# DEGREE_V3.net
KiCad netlist of a schematic drawn in EAGLE
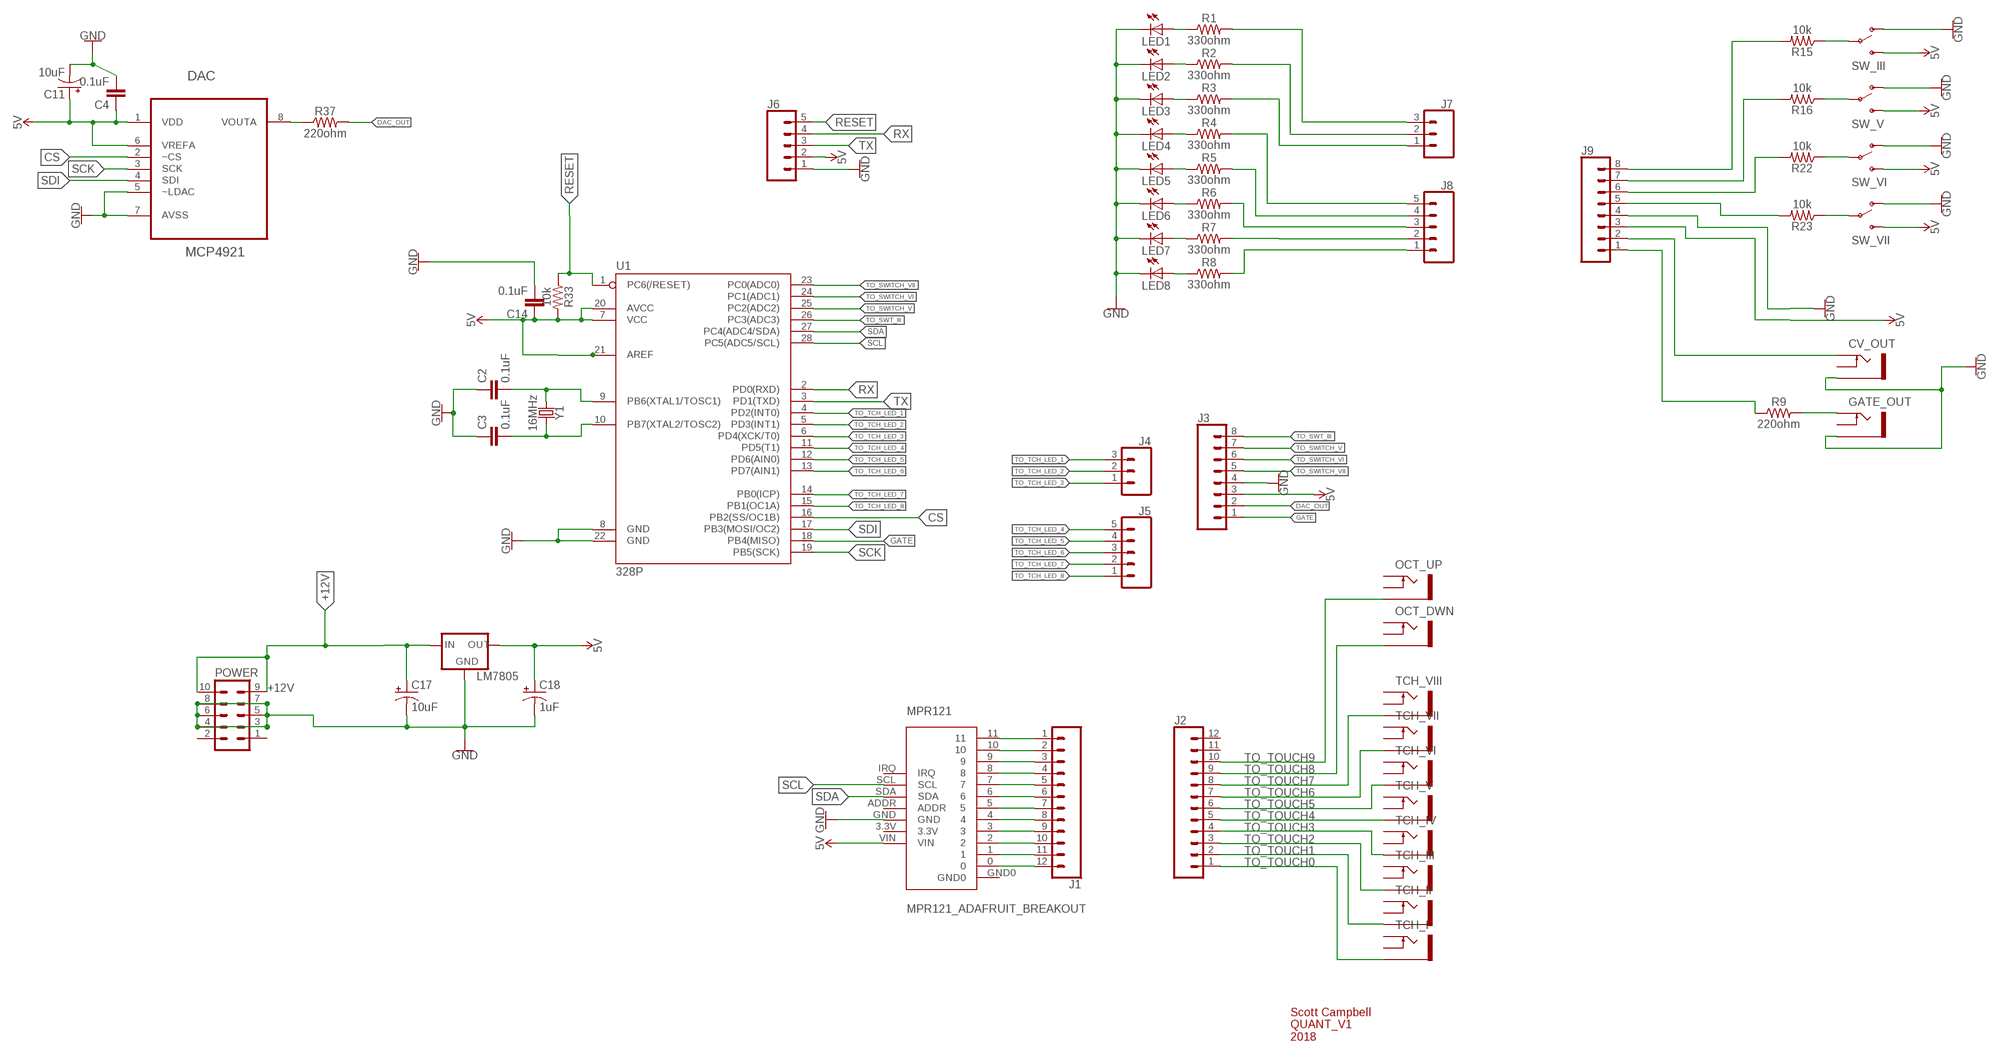
[diagram p0: schematic, sheet 1]

(export (version "E")
  (design (tool "Eeschema 10.0.6"))
  (components
    (comp (ref "C2")
      (value "0.1uF")
      (footprint "eagle-import:CAP-PTH-SMALL-KIT")
      (libsource (lib "eagle-import") (part "0.1UF-KIT-EZ-50V-20%"))
    )
    (comp (ref "C3")
      (value "0.1uF")
      (footprint "eagle-import:CAP-PTH-SMALL-KIT")
      (libsource (lib "eagle-import") (part "0.1UF-KIT-EZ-50V-20%"))
    )
    (comp (ref "C4")
      (value "0.1uF")
      (footprint "eagle-import:CAP-PTH-SMALL-KIT")
      (libsource (lib "eagle-import") (part "0.1UF-KIT-EZ-50V-20%"))
    )
    (comp (ref "C11")
      (value "10uF")
      (footprint "eagle-import:CPOL-RADIAL-2.5MM-5MM")
      (libsource (lib "eagle-import") (part "10UF-POLAR-RADIAL-2.5MM-25V-20%"))
    )
    (comp (ref "C14")
      (value "0.1uF")
      (footprint "eagle-import:CAP-PTH-SMALL-KIT")
      (libsource (lib "eagle-import") (part "0.1UF-KIT-EZ-50V-20%"))
    )
    (comp (ref "C17")
      (value "10uF")
      (footprint "eagle-import:CPOL-RADIAL-2.5MM-5MM")
      (libsource (lib "eagle-import") (part "10UF-POLAR-RADIAL-2.5MM-25V-20%"))
    )
    (comp (ref "C18")
      (value "1uF")
      (footprint "eagle-import:CPOL-RADIAL-2.5MM-5MM")
      (libsource (lib "eagle-import") (part "10UF-POLAR-RADIAL-2.5MM-25V-20%"))
    )
    (comp (ref "CV_OUT")
      (value "CV_OUT")
      (footprint "eagle-import:WQP-PJ301M-12_JACK")
      (libsource (lib "eagle-import") (part "THONKICONNNEW"))
    )
    (comp (ref "DAC")
      (value "MCP4921")
      (footprint "eagle-import:DIP08")
      (libsource (lib "eagle-import") (part "MCP4921"))
    )
    (comp (ref "GATE_OUT")
      (value "GATE_OUT")
      (footprint "eagle-import:WQP-PJ301M-12_JACK")
      (libsource (lib "eagle-import") (part "THONKICONNNEW"))
    )
    (comp (ref "J1")
      (value "CONN_12")
      (footprint "eagle-import:1X12")
      (libsource (lib "eagle-import") (part "CONN_12"))
    )
    (comp (ref "J2")
      (value "CONN_12")
      (footprint "eagle-import:1X12")
      (libsource (lib "eagle-import") (part "CONN_12"))
    )
    (comp (ref "J3")
      (value "CONN_08\"")
      (footprint "eagle-import:1X08")
      (libsource (lib "eagle-import") (part "CONN_08{dblquote}"))
    )
    (comp (ref "J4")
      (value "CONN_03")
      (footprint "eagle-import:1X03")
      (libsource (lib "eagle-import") (part "CONN_03"))
    )
    (comp (ref "J5")
      (value "CONN_05")
      (footprint "eagle-import:1X05")
      (libsource (lib "eagle-import") (part "CONN_05"))
    )
    (comp (ref "J6")
      (value "CONN_05")
      (footprint "eagle-import:1X05")
      (libsource (lib "eagle-import") (part "CONN_05"))
    )
    (comp (ref "J7")
      (value "CONN_03")
      (footprint "eagle-import:1X03")
      (libsource (lib "eagle-import") (part "CONN_03"))
    )
    (comp (ref "J8")
      (value "CONN_05")
      (footprint "eagle-import:1X05")
      (libsource (lib "eagle-import") (part "CONN_05"))
    )
    (comp (ref "J9")
      (value "CONN_08\"")
      (footprint "eagle-import:1X08")
      (libsource (lib "eagle-import") (part "CONN_08{dblquote}"))
    )
    (comp (ref "LED1")
      (value "LED3MM")
      (footprint "eagle-import:LED3MM")
      (libsource (lib "eagle-import") (part "LED3MM"))
    )
    (comp (ref "LED2")
      (value "LED3MM")
      (footprint "eagle-import:LED3MM")
      (libsource (lib "eagle-import") (part "LED3MM"))
    )
    (comp (ref "LED3")
      (value "LED3MM")
      (footprint "eagle-import:LED3MM")
      (libsource (lib "eagle-import") (part "LED3MM"))
    )
    (comp (ref "LED4")
      (value "LED3MM")
      (footprint "eagle-import:LED3MM")
      (libsource (lib "eagle-import") (part "LED3MM"))
    )
    (comp (ref "LED5")
      (value "LED3MM")
      (footprint "eagle-import:LED3MM")
      (libsource (lib "eagle-import") (part "LED3MM"))
    )
    (comp (ref "LED6")
      (value "LED3MM")
      (footprint "eagle-import:LED3MM")
      (libsource (lib "eagle-import") (part "LED3MM"))
    )
    (comp (ref "LED7")
      (value "LED3MM")
      (footprint "eagle-import:LED3MM")
      (libsource (lib "eagle-import") (part "LED3MM"))
    )
    (comp (ref "LED8")
      (value "LED3MM")
      (footprint "eagle-import:LED3MM")
      (libsource (lib "eagle-import") (part "LED3MM"))
    )
    (comp (ref "LM7805")
      (value "V_REG_78XXTO-92_UNTESTED")
      (footprint "eagle-import:TO-92")
      (libsource (lib "eagle-import") (part "V_REG_78XXTO-92_UNTESTED"))
    )
    (comp (ref "MPR121")
      (value "MPR121_ADAFRUIT_BREAKOUT")
      (footprint "eagle-import:MPR121_ADAFRUIT_BREAKOUT")
      (libsource (lib "eagle-import") (part "MPR121_ADAFRUIT_BREAKOUT"))
    )
    (comp (ref "OCT_DWN")
      (value "THONKICONN-ESSY")
      (footprint "eagle-import:THONKICONN-ESSY")
      (libsource (lib "eagle-import") (part "THONKICONN-ESSY"))
    )
    (comp (ref "OCT_UP")
      (value "THONKICONN-ESSY")
      (footprint "eagle-import:THONKICONN-ESSY")
      (libsource (lib "eagle-import") (part "THONKICONN-ESSY"))
    )
    (comp (ref "POWER")
      (value "EURO_POWER_HEADERREGULAR")
      (footprint "eagle-import:EURO_POWER_HEADER")
      (libsource (lib "eagle-import") (part "EURO_POWER_HEADERREGULAR"))
    )
    (comp (ref "R1")
      (value "330ohm")
      (footprint "eagle-import:AXIAL-0.3")
      (libsource (lib "eagle-import") (part "1KOHM-HORIZ-1/4W-5%"))
    )
    (comp (ref "R2")
      (value "330ohm")
      (footprint "eagle-import:AXIAL-0.3")
      (libsource (lib "eagle-import") (part "1KOHM-HORIZ-1/4W-5%"))
    )
    (comp (ref "R3")
      (value "330ohm")
      (footprint "eagle-import:AXIAL-0.3")
      (libsource (lib "eagle-import") (part "1KOHM-HORIZ-1/4W-5%"))
    )
    (comp (ref "R4")
      (value "330ohm")
      (footprint "eagle-import:AXIAL-0.3")
      (libsource (lib "eagle-import") (part "1KOHM-HORIZ-1/4W-5%"))
    )
    (comp (ref "R5")
      (value "330ohm")
      (footprint "eagle-import:AXIAL-0.3")
      (libsource (lib "eagle-import") (part "1KOHM-HORIZ-1/4W-5%"))
    )
    (comp (ref "R6")
      (value "330ohm")
      (footprint "eagle-import:AXIAL-0.3")
      (libsource (lib "eagle-import") (part "1KOHM-HORIZ-1/4W-5%"))
    )
    (comp (ref "R7")
      (value "330ohm")
      (footprint "eagle-import:AXIAL-0.3")
      (libsource (lib "eagle-import") (part "1KOHM-HORIZ-1/4W-5%"))
    )
    (comp (ref "R8")
      (value "330ohm")
      (footprint "eagle-import:AXIAL-0.3")
      (libsource (lib "eagle-import") (part "1KOHM-HORIZ-1/4W-5%"))
    )
    (comp (ref "R9")
      (value "220ohm")
      (footprint "eagle-import:HORIZONTAL_RESISTOR")
      (libsource (lib "eagle-import") (part "RESISTOR_HORZ"))
    )
    (comp (ref "R15")
      (value "10k")
      (footprint "eagle-import:HORIZONTAL_RESISTOR")
      (libsource (lib "eagle-import") (part "RESISTOR_HORZ"))
    )
    (comp (ref "R16")
      (value "10k")
      (footprint "eagle-import:HORIZONTAL_RESISTOR")
      (libsource (lib "eagle-import") (part "RESISTOR_HORZ"))
    )
    (comp (ref "R22")
      (value "10k")
      (footprint "eagle-import:HORIZONTAL_RESISTOR")
      (libsource (lib "eagle-import") (part "RESISTOR_HORZ"))
    )
    (comp (ref "R23")
      (value "10k")
      (footprint "eagle-import:HORIZONTAL_RESISTOR")
      (libsource (lib "eagle-import") (part "RESISTOR_HORZ"))
    )
    (comp (ref "R33")
      (value "10k")
      (footprint "eagle-import:HORIZONTAL_RESISTOR")
      (libsource (lib "eagle-import") (part "RESISTOR_HORZ"))
    )
    (comp (ref "R37")
      (value "220ohm")
      (footprint "eagle-import:VERTICAL_RESISTOR")
      (libsource (lib "eagle-import") (part "RESISTOR_VERT"))
    )
    (comp (ref "SW_III")
      (value "SUBMINI_SPDT")
      (footprint "eagle-import:SUBMINI_TOGGLE")
      (libsource (lib "eagle-import") (part "SUBMINI_SPDT"))
    )
    (comp (ref "SW_V")
      (value "SUBMINI_SPDT")
      (footprint "eagle-import:SUBMINI_TOGGLE")
      (libsource (lib "eagle-import") (part "SUBMINI_SPDT"))
    )
    (comp (ref "SW_VI")
      (value "SUBMINI_SPDT")
      (footprint "eagle-import:SUBMINI_TOGGLE")
      (libsource (lib "eagle-import") (part "SUBMINI_SPDT"))
    )
    (comp (ref "SW_VII")
      (value "SUBMINI_SPDT")
      (footprint "eagle-import:SUBMINI_TOGGLE")
      (libsource (lib "eagle-import") (part "SUBMINI_SPDT"))
    )
    (comp (ref "TCH_I")
      (value "THONKICONN-ESSY")
      (footprint "eagle-import:THONKICONN-ESSY")
      (libsource (lib "eagle-import") (part "THONKICONN-ESSY"))
    )
    (comp (ref "TCH_II")
      (value "THONKICONN-ESSY")
      (footprint "eagle-import:THONKICONN-ESSY")
      (libsource (lib "eagle-import") (part "THONKICONN-ESSY"))
    )
    (comp (ref "TCH_III")
      (value "THONKICONN-ESSY")
      (footprint "eagle-import:THONKICONN-ESSY")
      (libsource (lib "eagle-import") (part "THONKICONN-ESSY"))
    )
    (comp (ref "TCH_IV")
      (value "THONKICONN-ESSY")
      (footprint "eagle-import:THONKICONN-ESSY")
      (libsource (lib "eagle-import") (part "THONKICONN-ESSY"))
    )
    (comp (ref "TCH_V")
      (value "THONKICONN-ESSY")
      (footprint "eagle-import:THONKICONN-ESSY")
      (libsource (lib "eagle-import") (part "THONKICONN-ESSY"))
    )
    (comp (ref "TCH_VI")
      (value "THONKICONN-ESSY")
      (footprint "eagle-import:THONKICONN-ESSY")
      (libsource (lib "eagle-import") (part "THONKICONN-ESSY"))
    )
    (comp (ref "TCH_VII")
      (value "THONKICONN-ESSY")
      (footprint "eagle-import:THONKICONN-ESSY")
      (libsource (lib "eagle-import") (part "THONKICONN-ESSY"))
    )
    (comp (ref "TCH_VIII")
      (value "THONKICONN-ESSY")
      (footprint "eagle-import:THONKICONN-ESSY")
      (libsource (lib "eagle-import") (part "THONKICONN-ESSY"))
    )
    (comp (ref "U1")
      (value "328P")
      (footprint "eagle-import:DIP28")
      (libsource (lib "eagle-import") (part "ATMEGA328P_PDIP"))
    )
    (comp (ref "Y1")
      (value "16MHz")
      (footprint "eagle-import:HC49US")
      (libsource (lib "eagle-import") (part "CRYSTAL-16MHZPTH-HC49US"))
    )
  )
  (nets
    (net (code "1") (name "+12V") (class "Default")
      (node (ref "C17") (pin "1") (pinfunction "+_1") (pintype "passive"))
      (node (ref "LM7805") (pin "3") (pinfunction "IN_3") (pintype "input"))
      (node (ref "POWER") (pin "10") (pinfunction "10_10") (pintype "passive"))
      (node (ref "POWER") (pin "9") (pinfunction "9_9") (pintype "passive"))
    )
    (net (code "2") (name "/TO_TOUCH0") (class "Default")
      (node (ref "J2") (pin "1") (pinfunction "1_1") (pintype "passive"))
      (node (ref "TCH_I") (pin "P$3_SLEEVE") (pinfunction "SLEEVE_P$3_SLEEVE") (pintype "passive"))
    )
    (net (code "3") (name "/TO_TOUCH1") (class "Default")
      (node (ref "J2") (pin "2") (pinfunction "2_2") (pintype "passive"))
      (node (ref "TCH_II") (pin "P$3_SLEEVE") (pinfunction "SLEEVE_P$3_SLEEVE") (pintype "passive"))
    )
    (net (code "4") (name "/TO_TOUCH2") (class "Default")
      (node (ref "J2") (pin "3") (pinfunction "3_3") (pintype "passive"))
      (node (ref "TCH_III") (pin "P$3_SLEEVE") (pinfunction "SLEEVE_P$3_SLEEVE") (pintype "passive"))
    )
    (net (code "5") (name "/TO_TOUCH3") (class "Default")
      (node (ref "J2") (pin "4") (pinfunction "4_4") (pintype "passive"))
      (node (ref "TCH_IV") (pin "P$3_SLEEVE") (pinfunction "SLEEVE_P$3_SLEEVE") (pintype "passive"))
    )
    (net (code "6") (name "/TO_TOUCH4") (class "Default")
      (node (ref "J2") (pin "5") (pinfunction "5_5") (pintype "passive"))
      (node (ref "TCH_V") (pin "P$3_SLEEVE") (pinfunction "SLEEVE_P$3_SLEEVE") (pintype "passive"))
    )
    (net (code "7") (name "/TO_TOUCH5") (class "Default")
      (node (ref "J2") (pin "6") (pinfunction "6_6") (pintype "passive"))
      (node (ref "TCH_VI") (pin "P$3_SLEEVE") (pinfunction "SLEEVE_P$3_SLEEVE") (pintype "passive"))
    )
    (net (code "8") (name "/TO_TOUCH6") (class "Default")
      (node (ref "J2") (pin "7") (pinfunction "7_7") (pintype "passive"))
      (node (ref "TCH_VII") (pin "P$3_SLEEVE") (pinfunction "SLEEVE_P$3_SLEEVE") (pintype "passive"))
    )
    (net (code "9") (name "/TO_TOUCH7") (class "Default")
      (node (ref "J2") (pin "8") (pinfunction "8_8") (pintype "passive"))
      (node (ref "TCH_VIII") (pin "P$3_SLEEVE") (pinfunction "SLEEVE_P$3_SLEEVE") (pintype "passive"))
    )
    (net (code "10") (name "/TO_TOUCH8") (class "Default")
      (node (ref "J2") (pin "9") (pinfunction "9_9") (pintype "passive"))
      (node (ref "OCT_DWN") (pin "P$3_SLEEVE") (pinfunction "SLEEVE_P$3_SLEEVE") (pintype "passive"))
    )
    (net (code "11") (name "/TO_TOUCH9") (class "Default")
      (node (ref "J2") (pin "10") (pinfunction "10_10") (pintype "passive"))
      (node (ref "OCT_UP") (pin "P$3_SLEEVE") (pinfunction "SLEEVE_P$3_SLEEVE") (pintype "passive"))
    )
    (net (code "12") (name "5V") (class "Default")
      (node (ref "C11") (pin "1") (pinfunction "+_1") (pintype "passive"))
      (node (ref "C14") (pin "1") (pinfunction "1_1") (pintype "passive"))
      (node (ref "C18") (pin "1") (pinfunction "+_1") (pintype "passive"))
      (node (ref "C4") (pin "1") (pinfunction "1_1") (pintype "passive"))
      (node (ref "DAC") (pin "1") (pinfunction "VDD_1") (pintype "power_in"))
      (node (ref "DAC") (pin "6") (pinfunction "VREFA_6") (pintype "input"))
      (node (ref "J3") (pin "3") (pinfunction "3_3") (pintype "passive"))
      (node (ref "J6") (pin "2") (pinfunction "2_2") (pintype "passive"))
      (node (ref "J9") (pin "3") (pinfunction "3_3") (pintype "passive"))
      (node (ref "LM7805") (pin "1") (pinfunction "OUT_1") (pintype "passive"))
      (node (ref "MPR121") (pin "VIN") (pinfunction "VIN_VIN") (pintype "bidirectional"))
      (node (ref "R33") (pin "2") (pinfunction "2_2") (pintype "passive"))
      (node (ref "SW_III") (pin "3") (pinfunction "S_3") (pintype "passive"))
      (node (ref "SW_V") (pin "3") (pinfunction "S_3") (pintype "passive"))
      (node (ref "SW_VI") (pin "3") (pinfunction "S_3") (pintype "passive"))
      (node (ref "SW_VII") (pin "3") (pinfunction "S_3") (pintype "passive"))
      (node (ref "U1") (pin "20") (pinfunction "AVCC_20") (pintype "bidirectional"))
      (node (ref "U1") (pin "21") (pinfunction "AREF_21") (pintype "bidirectional"))
      (node (ref "U1") (pin "7") (pinfunction "VCC_7") (pintype "bidirectional"))
    )
    (net (code "13") (name "CS") (class "Default")
      (node (ref "DAC") (pin "2") (pinfunction "~{CS}_2") (pintype "input"))
      (node (ref "U1") (pin "16") (pinfunction "PB2(SS/OC1B)_16") (pintype "bidirectional"))
    )
    (net (code "14") (name "DAC_OUT") (class "Default")
      (node (ref "J3") (pin "2") (pinfunction "2_2") (pintype "passive"))
      (node (ref "R37") (pin "2") (pinfunction "2_2") (pintype "passive"))
    )
    (net (code "15") (name "GATE") (class "Default")
      (node (ref "J3") (pin "1") (pinfunction "1_1") (pintype "passive"))
      (node (ref "U1") (pin "18") (pinfunction "PB4(MISO)_18") (pintype "bidirectional"))
    )
    (net (code "16") (name "GND") (class "Default")
      (node (ref "C11") (pin "2") (pinfunction "-_2") (pintype "passive"))
      (node (ref "C14") (pin "2") (pinfunction "2_2") (pintype "passive"))
      (node (ref "C17") (pin "2") (pinfunction "-_2") (pintype "passive"))
      (node (ref "C18") (pin "2") (pinfunction "-_2") (pintype "passive"))
      (node (ref "C2") (pin "1") (pinfunction "1_1") (pintype "passive"))
      (node (ref "C3") (pin "1") (pinfunction "1_1") (pintype "passive"))
      (node (ref "C4") (pin "2") (pinfunction "2_2") (pintype "passive"))
      (node (ref "CV_OUT") (pin "P$3_SLEEVE") (pinfunction "SLEEVE_P$3_SLEEVE") (pintype "passive"))
      (node (ref "DAC") (pin "5") (pinfunction "~{LDAC}_5") (pintype "input"))
      (node (ref "DAC") (pin "7") (pinfunction "AVSS_7") (pintype "passive"))
      (node (ref "GATE_OUT") (pin "P$3_SLEEVE") (pinfunction "SLEEVE_P$3_SLEEVE") (pintype "passive"))
      (node (ref "J3") (pin "4") (pinfunction "4_4") (pintype "passive"))
      (node (ref "J6") (pin "1") (pinfunction "1_1") (pintype "passive"))
      (node (ref "J9") (pin "4") (pinfunction "4_4") (pintype "passive"))
      (node (ref "LED1") (pin "K") (pinfunction "C_K") (pintype "passive"))
      (node (ref "LED2") (pin "K") (pinfunction "C_K") (pintype "passive"))
      (node (ref "LED3") (pin "K") (pinfunction "C_K") (pintype "passive"))
      (node (ref "LED4") (pin "K") (pinfunction "C_K") (pintype "passive"))
      (node (ref "LED5") (pin "K") (pinfunction "C_K") (pintype "passive"))
      (node (ref "LED6") (pin "K") (pinfunction "C_K") (pintype "passive"))
      (node (ref "LED7") (pin "K") (pinfunction "C_K") (pintype "passive"))
      (node (ref "LED8") (pin "K") (pinfunction "C_K") (pintype "passive"))
      (node (ref "LM7805") (pin "2") (pinfunction "GND_2") (pintype "input"))
      (node (ref "MPR121") (pin "GND") (pinfunction "GND_GND") (pintype "bidirectional"))
      (node (ref "POWER") (pin "3") (pinfunction "3_3") (pintype "passive"))
      (node (ref "POWER") (pin "4") (pinfunction "4_4") (pintype "passive"))
      (node (ref "POWER") (pin "5") (pinfunction "5_5") (pintype "passive"))
      (node (ref "POWER") (pin "6") (pinfunction "6_6") (pintype "passive"))
      (node (ref "POWER") (pin "7") (pinfunction "7_7") (pintype "passive"))
      (node (ref "POWER") (pin "8") (pinfunction "8_8") (pintype "passive"))
      (node (ref "SW_III") (pin "1") (pinfunction "O_1") (pintype "passive"))
      (node (ref "SW_V") (pin "1") (pinfunction "O_1") (pintype "passive"))
      (node (ref "SW_VI") (pin "1") (pinfunction "O_1") (pintype "passive"))
      (node (ref "SW_VII") (pin "1") (pinfunction "O_1") (pintype "passive"))
      (node (ref "U1") (pin "22") (pinfunction "GND_22") (pintype "bidirectional"))
      (node (ref "U1") (pin "8") (pinfunction "GND_8") (pintype "bidirectional"))
    )
    (net (code "17") (name "Net-(CV_OUT-TIP)") (class "Default")
      (node (ref "CV_OUT") (pin "P$1_TIP") (pinfunction "TIP_P$1_TIP") (pintype "passive"))
      (node (ref "J9") (pin "2") (pinfunction "2_2") (pintype "passive"))
    )
    (net (code "18") (name "Net-(DAC-VOUTA)") (class "Default")
      (node (ref "DAC") (pin "8") (pinfunction "VOUTA_8") (pintype "output"))
      (node (ref "R37") (pin "1") (pinfunction "1_1") (pintype "passive"))
    )
    (net (code "19") (name "Net-(GATE_OUT-TIP)") (class "Default")
      (node (ref "GATE_OUT") (pin "P$1_TIP") (pinfunction "TIP_P$1_TIP") (pintype "passive"))
      (node (ref "R9") (pin "2") (pinfunction "2_2") (pintype "passive"))
    )
    (net (code "20") (name "Net-(J1-Pad1)") (class "Default")
      (node (ref "J1") (pin "1") (pinfunction "1_1") (pintype "passive"))
      (node (ref "MPR121") (pin "11") (pinfunction "11_11") (pintype "bidirectional"))
    )
    (net (code "21") (name "Net-(J1-Pad2)") (class "Default")
      (node (ref "J1") (pin "2") (pinfunction "2_2") (pintype "passive"))
      (node (ref "MPR121") (pin "10") (pinfunction "10_10") (pintype "bidirectional"))
    )
    (net (code "22") (name "Net-(J1-Pad3)") (class "Default")
      (node (ref "J1") (pin "3") (pinfunction "3_3") (pintype "passive"))
      (node (ref "MPR121") (pin "9") (pinfunction "9_9") (pintype "bidirectional"))
    )
    (net (code "23") (name "Net-(J1-Pad4)") (class "Default")
      (node (ref "J1") (pin "4") (pinfunction "4_4") (pintype "passive"))
      (node (ref "MPR121") (pin "8") (pinfunction "8_8") (pintype "bidirectional"))
    )
    (net (code "24") (name "Net-(J1-Pad5)") (class "Default")
      (node (ref "J1") (pin "5") (pinfunction "5_5") (pintype "passive"))
      (node (ref "MPR121") (pin "7") (pinfunction "7_7") (pintype "bidirectional"))
    )
    (net (code "25") (name "Net-(J1-Pad6)") (class "Default")
      (node (ref "J1") (pin "6") (pinfunction "6_6") (pintype "passive"))
      (node (ref "MPR121") (pin "6") (pinfunction "6_6") (pintype "bidirectional"))
    )
    (net (code "26") (name "Net-(J1-Pad7)") (class "Default")
      (node (ref "J1") (pin "7") (pinfunction "7_7") (pintype "passive"))
      (node (ref "MPR121") (pin "5") (pinfunction "5_5") (pintype "bidirectional"))
    )
    (net (code "27") (name "Net-(J1-Pad8)") (class "Default")
      (node (ref "J1") (pin "8") (pinfunction "8_8") (pintype "passive"))
      (node (ref "MPR121") (pin "4") (pinfunction "4_4") (pintype "bidirectional"))
    )
    (net (code "28") (name "Net-(J1-Pad9)") (class "Default")
      (node (ref "J1") (pin "9") (pinfunction "9_9") (pintype "passive"))
      (node (ref "MPR121") (pin "3") (pinfunction "3_3") (pintype "bidirectional"))
    )
    (net (code "29") (name "Net-(J1-Pad10)") (class "Default")
      (node (ref "J1") (pin "10") (pinfunction "10_10") (pintype "passive"))
      (node (ref "MPR121") (pin "2") (pinfunction "2_2") (pintype "bidirectional"))
    )
    (net (code "30") (name "Net-(J1-Pad11)") (class "Default")
      (node (ref "J1") (pin "11") (pinfunction "11_11") (pintype "passive"))
      (node (ref "MPR121") (pin "1") (pinfunction "1_1") (pintype "bidirectional"))
    )
    (net (code "31") (name "Net-(J1-Pad12)") (class "Default")
      (node (ref "J1") (pin "12") (pinfunction "12_12") (pintype "passive"))
      (node (ref "MPR121") (pin "0") (pinfunction "0_0") (pintype "bidirectional"))
    )
    (net (code "32") (name "Net-(J9-Pad1)") (class "Default")
      (node (ref "J9") (pin "1") (pinfunction "1_1") (pintype "passive"))
      (node (ref "R9") (pin "1") (pinfunction "1_1") (pintype "passive"))
    )
    (net (code "33") (name "Net-(J9-Pad5)") (class "Default")
      (node (ref "J9") (pin "5") (pinfunction "5_5") (pintype "passive"))
      (node (ref "R23") (pin "2") (pinfunction "2_2") (pintype "passive"))
    )
    (net (code "34") (name "Net-(J9-Pad6)") (class "Default")
      (node (ref "J9") (pin "6") (pinfunction "6_6") (pintype "passive"))
      (node (ref "R22") (pin "2") (pinfunction "2_2") (pintype "passive"))
    )
    (net (code "35") (name "Net-(J9-Pad7)") (class "Default")
      (node (ref "J9") (pin "7") (pinfunction "7_7") (pintype "passive"))
      (node (ref "R16") (pin "2") (pinfunction "2_2") (pintype "passive"))
    )
    (net (code "36") (name "Net-(J9-Pad8)") (class "Default")
      (node (ref "J9") (pin "8") (pinfunction "8_8") (pintype "passive"))
      (node (ref "R15") (pin "2") (pinfunction "2_2") (pintype "passive"))
    )
    (net (code "37") (name "Net-(R1-1)") (class "Default")
      (node (ref "LED1") (pin "A") (pinfunction "A_A") (pintype "passive"))
      (node (ref "R1") (pin "P$1") (pinfunction "1_P$1") (pintype "passive"))
    )
    (net (code "38") (name "Net-(R1-2)") (class "Default")
      (node (ref "J7") (pin "3") (pinfunction "3_3") (pintype "passive"))
      (node (ref "R1") (pin "P$2") (pinfunction "2_P$2") (pintype "passive"))
    )
    (net (code "39") (name "Net-(R2-1)") (class "Default")
      (node (ref "LED2") (pin "A") (pinfunction "A_A") (pintype "passive"))
      (node (ref "R2") (pin "P$1") (pinfunction "1_P$1") (pintype "passive"))
    )
    (net (code "40") (name "Net-(R2-2)") (class "Default")
      (node (ref "J7") (pin "2") (pinfunction "2_2") (pintype "passive"))
      (node (ref "R2") (pin "P$2") (pinfunction "2_P$2") (pintype "passive"))
    )
    (net (code "41") (name "Net-(R3-1)") (class "Default")
      (node (ref "LED3") (pin "A") (pinfunction "A_A") (pintype "passive"))
      (node (ref "R3") (pin "P$1") (pinfunction "1_P$1") (pintype "passive"))
    )
    (net (code "42") (name "Net-(R3-2)") (class "Default")
      (node (ref "J7") (pin "1") (pinfunction "1_1") (pintype "passive"))
      (node (ref "R3") (pin "P$2") (pinfunction "2_P$2") (pintype "passive"))
    )
    (net (code "43") (name "Net-(R4-1)") (class "Default")
      (node (ref "LED4") (pin "A") (pinfunction "A_A") (pintype "passive"))
      (node (ref "R4") (pin "P$1") (pinfunction "1_P$1") (pintype "passive"))
    )
    (net (code "44") (name "Net-(R4-2)") (class "Default")
      (node (ref "J8") (pin "5") (pinfunction "5_5") (pintype "passive"))
      (node (ref "R4") (pin "P$2") (pinfunction "2_P$2") (pintype "passive"))
    )
    (net (code "45") (name "Net-(R5-1)") (class "Default")
      (node (ref "LED5") (pin "A") (pinfunction "A_A") (pintype "passive"))
      (node (ref "R5") (pin "P$1") (pinfunction "1_P$1") (pintype "passive"))
    )
    (net (code "46") (name "Net-(R5-2)") (class "Default")
      (node (ref "J8") (pin "4") (pinfunction "4_4") (pintype "passive"))
      (node (ref "R5") (pin "P$2") (pinfunction "2_P$2") (pintype "passive"))
    )
    (net (code "47") (name "Net-(R6-1)") (class "Default")
      (node (ref "LED6") (pin "A") (pinfunction "A_A") (pintype "passive"))
      (node (ref "R6") (pin "P$1") (pinfunction "1_P$1") (pintype "passive"))
    )
    (net (code "48") (name "Net-(R6-2)") (class "Default")
      (node (ref "J8") (pin "3") (pinfunction "3_3") (pintype "passive"))
      (node (ref "R6") (pin "P$2") (pinfunction "2_P$2") (pintype "passive"))
    )
    (net (code "49") (name "Net-(R7-1)") (class "Default")
      (node (ref "LED7") (pin "A") (pinfunction "A_A") (pintype "passive"))
      (node (ref "R7") (pin "P$1") (pinfunction "1_P$1") (pintype "passive"))
    )
    (net (code "50") (name "Net-(R7-2)") (class "Default")
      (node (ref "J8") (pin "2") (pinfunction "2_2") (pintype "passive"))
      (node (ref "R7") (pin "P$2") (pinfunction "2_P$2") (pintype "passive"))
    )
    (net (code "51") (name "Net-(R8-1)") (class "Default")
      (node (ref "LED8") (pin "A") (pinfunction "A_A") (pintype "passive"))
      (node (ref "R8") (pin "P$1") (pinfunction "1_P$1") (pintype "passive"))
    )
    (net (code "52") (name "Net-(R8-2)") (class "Default")
      (node (ref "J8") (pin "1") (pinfunction "1_1") (pintype "passive"))
      (node (ref "R8") (pin "P$2") (pinfunction "2_P$2") (pintype "passive"))
    )
    (net (code "53") (name "Net-(SW_III-COMMON)") (class "Default")
      (node (ref "R15") (pin "1") (pinfunction "1_1") (pintype "passive"))
      (node (ref "SW_III") (pin "COM") (pinfunction "COMMON_COM") (pintype "passive"))
    )
    (net (code "54") (name "Net-(SW_V-COMMON)") (class "Default")
      (node (ref "R16") (pin "1") (pinfunction "1_1") (pintype "passive"))
      (node (ref "SW_V") (pin "COM") (pinfunction "COMMON_COM") (pintype "passive"))
    )
    (net (code "55") (name "Net-(SW_VI-COMMON)") (class "Default")
      (node (ref "R22") (pin "1") (pinfunction "1_1") (pintype "passive"))
      (node (ref "SW_VI") (pin "COM") (pinfunction "COMMON_COM") (pintype "passive"))
    )
    (net (code "56") (name "Net-(SW_VII-COMMON)") (class "Default")
      (node (ref "R23") (pin "1") (pinfunction "1_1") (pintype "passive"))
      (node (ref "SW_VII") (pin "COM") (pinfunction "COMMON_COM") (pintype "passive"))
    )
    (net (code "57") (name "Net-(U1-PB6(XTAL1{slash}TOSC1))") (class "Default")
      (node (ref "C2") (pin "2") (pinfunction "2_2") (pintype "passive"))
      (node (ref "U1") (pin "9") (pinfunction "PB6(XTAL1/TOSC1)_9") (pintype "bidirectional"))
      (node (ref "Y1") (pin "1") (pinfunction "1_1") (pintype "passive"))
    )
    (net (code "58") (name "Net-(U1-PB7(XTAL2{slash}TOSC2))") (class "Default")
      (node (ref "C3") (pin "2") (pinfunction "2_2") (pintype "passive"))
      (node (ref "U1") (pin "10") (pinfunction "PB7(XTAL2/TOSC2)_10") (pintype "bidirectional"))
      (node (ref "Y1") (pin "2") (pinfunction "2_2") (pintype "passive"))
    )
    (net (code "59") (name "RESET") (class "Default")
      (node (ref "J6") (pin "5") (pinfunction "5_5") (pintype "passive"))
      (node (ref "R33") (pin "1") (pinfunction "1_1") (pintype "passive"))
      (node (ref "U1") (pin "1") (pinfunction "PC6(/RESET)_1") (pintype "bidirectional"))
    )
    (net (code "60") (name "RX") (class "Default")
      (node (ref "J6") (pin "4") (pinfunction "4_4") (pintype "passive"))
      (node (ref "U1") (pin "2") (pinfunction "PD0(RXD)_2") (pintype "bidirectional"))
    )
    (net (code "61") (name "SCK") (class "Default")
      (node (ref "DAC") (pin "3") (pinfunction "SCK_3") (pintype "input"))
      (node (ref "U1") (pin "19") (pinfunction "PB5(SCK)_19") (pintype "bidirectional"))
    )
    (net (code "62") (name "SCL") (class "Default")
      (node (ref "MPR121") (pin "SCL") (pinfunction "SCL_SCL") (pintype "bidirectional"))
      (node (ref "U1") (pin "28") (pinfunction "PC5(ADC5/SCL)_28") (pintype "bidirectional"))
    )
    (net (code "63") (name "SDA") (class "Default")
      (node (ref "MPR121") (pin "SDA") (pinfunction "SDA_SDA") (pintype "bidirectional"))
      (node (ref "U1") (pin "27") (pinfunction "PC4(ADC4/SDA)_27") (pintype "bidirectional"))
    )
    (net (code "64") (name "SDI") (class "Default")
      (node (ref "DAC") (pin "4") (pinfunction "SDI_4") (pintype "input"))
      (node (ref "U1") (pin "17") (pinfunction "PB3(MOSI/OC2)_17") (pintype "bidirectional"))
    )
    (net (code "65") (name "TO_SWITCH_V") (class "Default")
      (node (ref "J3") (pin "7") (pinfunction "7_7") (pintype "passive"))
      (node (ref "U1") (pin "25") (pinfunction "PC2(ADC2)_25") (pintype "bidirectional"))
    )
    (net (code "66") (name "TO_SWITCH_VI") (class "Default")
      (node (ref "J3") (pin "6") (pinfunction "6_6") (pintype "passive"))
      (node (ref "U1") (pin "24") (pinfunction "PC1(ADC1)_24") (pintype "bidirectional"))
    )
    (net (code "67") (name "TO_SWITCH_VII") (class "Default")
      (node (ref "J3") (pin "5") (pinfunction "5_5") (pintype "passive"))
      (node (ref "U1") (pin "23") (pinfunction "PC0(ADC0)_23") (pintype "bidirectional"))
    )
    (net (code "68") (name "TO_SWT_III") (class "Default")
      (node (ref "J3") (pin "8") (pinfunction "8_8") (pintype "passive"))
      (node (ref "U1") (pin "26") (pinfunction "PC3(ADC3)_26") (pintype "bidirectional"))
    )
    (net (code "69") (name "TO_TCH_LED_1") (class "Default")
      (node (ref "J4") (pin "3") (pinfunction "3_3") (pintype "passive"))
      (node (ref "U1") (pin "4") (pinfunction "PD2(INT0)_4") (pintype "bidirectional"))
    )
    (net (code "70") (name "TO_TCH_LED_2") (class "Default")
      (node (ref "J4") (pin "2") (pinfunction "2_2") (pintype "passive"))
      (node (ref "U1") (pin "5") (pinfunction "PD3(INT1)_5") (pintype "bidirectional"))
    )
    (net (code "71") (name "TO_TCH_LED_3") (class "Default")
      (node (ref "J4") (pin "1") (pinfunction "1_1") (pintype "passive"))
      (node (ref "U1") (pin "6") (pinfunction "PD4(XCK/T0)_6") (pintype "bidirectional"))
    )
    (net (code "72") (name "TO_TCH_LED_4") (class "Default")
      (node (ref "J5") (pin "5") (pinfunction "5_5") (pintype "passive"))
      (node (ref "U1") (pin "11") (pinfunction "PD5(T1)_11") (pintype "bidirectional"))
    )
    (net (code "73") (name "TO_TCH_LED_5") (class "Default")
      (node (ref "J5") (pin "4") (pinfunction "4_4") (pintype "passive"))
      (node (ref "U1") (pin "12") (pinfunction "PD6(AIN0)_12") (pintype "bidirectional"))
    )
    (net (code "74") (name "TO_TCH_LED_6") (class "Default")
      (node (ref "J5") (pin "3") (pinfunction "3_3") (pintype "passive"))
      (node (ref "U1") (pin "13") (pinfunction "PD7(AIN1)_13") (pintype "bidirectional"))
    )
    (net (code "75") (name "TO_TCH_LED_7") (class "Default")
      (node (ref "J5") (pin "2") (pinfunction "2_2") (pintype "passive"))
      (node (ref "U1") (pin "14") (pinfunction "PB0(ICP)_14") (pintype "bidirectional"))
    )
    (net (code "76") (name "TO_TCH_LED_8") (class "Default")
      (node (ref "J5") (pin "1") (pinfunction "1_1") (pintype "passive"))
      (node (ref "U1") (pin "15") (pinfunction "PB1(OC1A)_15") (pintype "bidirectional"))
    )
    (net (code "77") (name "TX") (class "Default")
      (node (ref "J6") (pin "3") (pinfunction "3_3") (pintype "passive"))
      (node (ref "U1") (pin "3") (pinfunction "PD1(TXD)_3") (pintype "bidirectional"))
    )
    (net (code "78") (name "unconnected-(CV_OUT-SWITCH-PadP$2_SWITCH)") (class "Default")
      (node (ref "CV_OUT") (pin "P$2_SWITCH") (pinfunction "SWITCH_P$2_SWITCH") (pintype "passive"))
    )
    (net (code "79") (name "unconnected-(GATE_OUT-SWITCH-PadP$2_SWITCH)") (class "Default")
      (node (ref "GATE_OUT") (pin "P$2_SWITCH") (pinfunction "SWITCH_P$2_SWITCH") (pintype "passive"))
    )
    (net (code "80") (name "unconnected-(J2-Pad11)") (class "Default")
      (node (ref "J2") (pin "11") (pinfunction "11_11") (pintype "passive"))
    )
    (net (code "81") (name "unconnected-(J2-Pad12)") (class "Default")
      (node (ref "J2") (pin "12") (pinfunction "12_12") (pintype "passive"))
    )
    (net (code "82") (name "unconnected-(MPR121-Pad3.3V)") (class "Default")
      (node (ref "MPR121") (pin "3.3V") (pinfunction "3.3V_3.3V") (pintype "bidirectional"))
    )
    (net (code "83") (name "unconnected-(MPR121-PadADDR)") (class "Default")
      (node (ref "MPR121") (pin "ADDR") (pinfunction "ADDR_ADDR") (pintype "bidirectional"))
    )
    (net (code "84") (name "unconnected-(MPR121-PadGND0)") (class "Default")
      (node (ref "MPR121") (pin "GND0") (pinfunction "GND0_GND0") (pintype "bidirectional"))
    )
    (net (code "85") (name "unconnected-(MPR121-PadIRQ)") (class "Default")
      (node (ref "MPR121") (pin "IRQ") (pinfunction "IRQ_IRQ") (pintype "bidirectional"))
    )
    (net (code "86") (name "unconnected-(OCT_DWN-SWITCH-PadP$2_SWITCH)") (class "Default")
      (node (ref "OCT_DWN") (pin "P$2_SWITCH") (pinfunction "SWITCH_P$2_SWITCH") (pintype "passive"))
    )
    (net (code "87") (name "unconnected-(OCT_DWN-TIP-PadP$1_TIP)") (class "Default")
      (node (ref "OCT_DWN") (pin "P$1_TIP") (pinfunction "TIP_P$1_TIP") (pintype "passive"))
    )
    (net (code "88") (name "unconnected-(OCT_UP-SWITCH-PadP$2_SWITCH)") (class "Default")
      (node (ref "OCT_UP") (pin "P$2_SWITCH") (pinfunction "SWITCH_P$2_SWITCH") (pintype "passive"))
    )
    (net (code "89") (name "unconnected-(OCT_UP-TIP-PadP$1_TIP)") (class "Default")
      (node (ref "OCT_UP") (pin "P$1_TIP") (pinfunction "TIP_P$1_TIP") (pintype "passive"))
    )
    (net (code "90") (name "unconnected-(POWER-Pad1)") (class "Default")
      (node (ref "POWER") (pin "1") (pinfunction "1_1") (pintype "passive"))
    )
    (net (code "91") (name "unconnected-(POWER-Pad2)") (class "Default")
      (node (ref "POWER") (pin "2") (pinfunction "2_2") (pintype "passive"))
    )
    (net (code "92") (name "unconnected-(TCH_I-SWITCH-PadP$2_SWITCH)") (class "Default")
      (node (ref "TCH_I") (pin "P$2_SWITCH") (pinfunction "SWITCH_P$2_SWITCH") (pintype "passive"))
    )
    (net (code "93") (name "unconnected-(TCH_I-TIP-PadP$1_TIP)") (class "Default")
      (node (ref "TCH_I") (pin "P$1_TIP") (pinfunction "TIP_P$1_TIP") (pintype "passive"))
    )
    (net (code "94") (name "unconnected-(TCH_II-SWITCH-PadP$2_SWITCH)") (class "Default")
      (node (ref "TCH_II") (pin "P$2_SWITCH") (pinfunction "SWITCH_P$2_SWITCH") (pintype "passive"))
    )
    (net (code "95") (name "unconnected-(TCH_II-TIP-PadP$1_TIP)") (class "Default")
      (node (ref "TCH_II") (pin "P$1_TIP") (pinfunction "TIP_P$1_TIP") (pintype "passive"))
    )
    (net (code "96") (name "unconnected-(TCH_III-SWITCH-PadP$2_SWITCH)") (class "Default")
      (node (ref "TCH_III") (pin "P$2_SWITCH") (pinfunction "SWITCH_P$2_SWITCH") (pintype "passive"))
    )
    (net (code "97") (name "unconnected-(TCH_III-TIP-PadP$1_TIP)") (class "Default")
      (node (ref "TCH_III") (pin "P$1_TIP") (pinfunction "TIP_P$1_TIP") (pintype "passive"))
    )
    (net (code "98") (name "unconnected-(TCH_IV-SWITCH-PadP$2_SWITCH)") (class "Default")
      (node (ref "TCH_IV") (pin "P$2_SWITCH") (pinfunction "SWITCH_P$2_SWITCH") (pintype "passive"))
    )
    (net (code "99") (name "unconnected-(TCH_IV-TIP-PadP$1_TIP)") (class "Default")
      (node (ref "TCH_IV") (pin "P$1_TIP") (pinfunction "TIP_P$1_TIP") (pintype "passive"))
    )
    (net (code "100") (name "unconnected-(TCH_V-SWITCH-PadP$2_SWITCH)") (class "Default")
      (node (ref "TCH_V") (pin "P$2_SWITCH") (pinfunction "SWITCH_P$2_SWITCH") (pintype "passive"))
    )
    (net (code "101") (name "unconnected-(TCH_V-TIP-PadP$1_TIP)") (class "Default")
      (node (ref "TCH_V") (pin "P$1_TIP") (pinfunction "TIP_P$1_TIP") (pintype "passive"))
    )
    (net (code "102") (name "unconnected-(TCH_VI-SWITCH-PadP$2_SWITCH)") (class "Default")
      (node (ref "TCH_VI") (pin "P$2_SWITCH") (pinfunction "SWITCH_P$2_SWITCH") (pintype "passive"))
    )
    (net (code "103") (name "unconnected-(TCH_VI-TIP-PadP$1_TIP)") (class "Default")
      (node (ref "TCH_VI") (pin "P$1_TIP") (pinfunction "TIP_P$1_TIP") (pintype "passive"))
    )
    (net (code "104") (name "unconnected-(TCH_VII-SWITCH-PadP$2_SWITCH)") (class "Default")
      (node (ref "TCH_VII") (pin "P$2_SWITCH") (pinfunction "SWITCH_P$2_SWITCH") (pintype "passive"))
    )
    (net (code "105") (name "unconnected-(TCH_VII-TIP-PadP$1_TIP)") (class "Default")
      (node (ref "TCH_VII") (pin "P$1_TIP") (pinfunction "TIP_P$1_TIP") (pintype "passive"))
    )
    (net (code "106") (name "unconnected-(TCH_VIII-SWITCH-PadP$2_SWITCH)") (class "Default")
      (node (ref "TCH_VIII") (pin "P$2_SWITCH") (pinfunction "SWITCH_P$2_SWITCH") (pintype "passive"))
    )
    (net (code "107") (name "unconnected-(TCH_VIII-TIP-PadP$1_TIP)") (class "Default")
      (node (ref "TCH_VIII") (pin "P$1_TIP") (pinfunction "TIP_P$1_TIP") (pintype "passive"))
    )
  )
)
